# Interfaces.net
KiCad netlist of a schematic drawn in Altium Designer
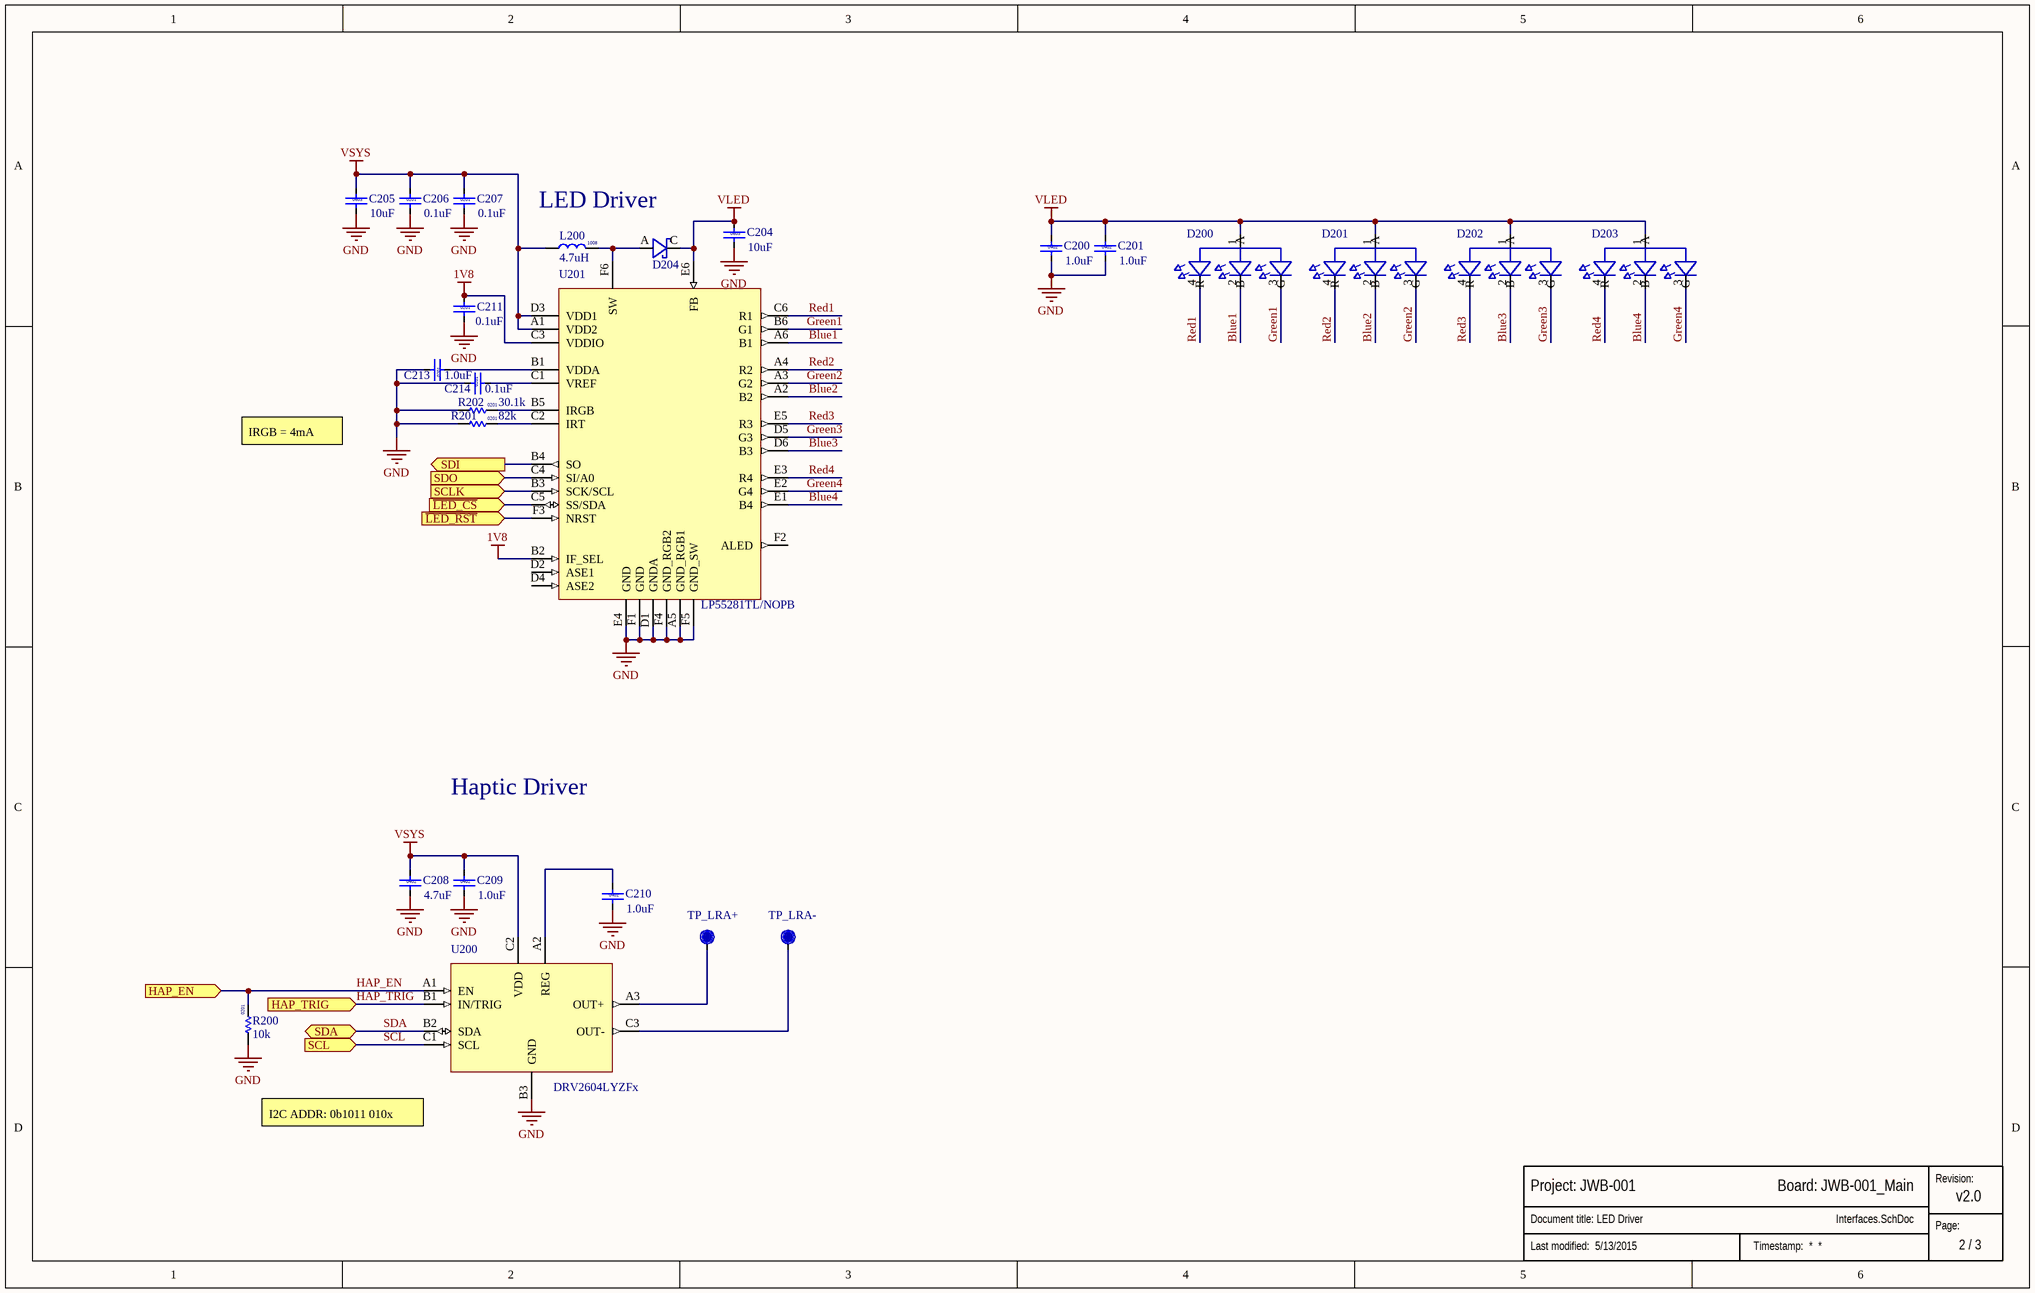
[diagram p0: Interfaces.SchDoc]

(export (version "E")
  (design (tool "Eeschema 10.0.6"))
  (components
    (comp (ref "C200")
      (value "1.0uF")
      (footprint "Cap 0402 HD")
      (description "Cap, Ceramic 1.0uF 10V 10% X5R 0402")
      (fields
        (field (name "SIZE") "0402")
        (field (name "PART NUMBER") "Cap 0402 1.0uF 10V")
        (field (name "TOLERANCE") "10%")
        (field (name "ADDED BY") "Jeremy D")
        (field (name "CHECKED BY") "Paul B")
      )
      (libsource (lib "Rigado_AltiumLib") (part "Cap Chip"))
    )
    (comp (ref "C201")
      (value "1.0uF")
      (footprint "Cap 0402 HD")
      (description "Cap, Ceramic 1.0uF 10V 10% X5R 0402")
      (fields
        (field (name "SIZE") "0402")
        (field (name "PART NUMBER") "Cap 0402 1.0uF 10V")
        (field (name "TOLERANCE") "10%")
        (field (name "ADDED BY") "Jeremy D")
        (field (name "CHECKED BY") "Paul B")
      )
      (libsource (lib "Rigado_AltiumLib") (part "Cap Chip"))
    )
    (comp (ref "C204")
      (value "10uF")
      (footprint "Cap 0603")
      (description "Cap, Ceramimic 10uF 10V 20% X5R 0603")
      (fields
        (field (name "SIZE") "0603")
        (field (name "PART NUMBER") "Cap 0603 10uF 10V")
        (field (name "TOLERANCE") "20%")
        (field (name "ADDED BY") "Jeremy D")
        (field (name "CHECKED BY") "Cam N")
      )
      (libsource (lib "Rigado_AltiumLib") (part "Cap Chip"))
    )
    (comp (ref "C205")
      (value "10uF")
      (footprint "Cap 0603")
      (description "Cap, Ceramimic 10uF 10V 20% X5R 0603")
      (fields
        (field (name "SIZE") "0603")
        (field (name "PART NUMBER") "Cap 0603 10uF 10V")
        (field (name "TOLERANCE") "20%")
        (field (name "ADDED BY") "Jeremy D")
        (field (name "CHECKED BY") "Cam N")
      )
      (libsource (lib "Rigado_AltiumLib") (part "Cap Chip"))
    )
    (comp (ref "C206")
      (value "0.1uF")
      (footprint "Cap 0201 HD")
      (description "Cap, Ceramic 0.1uF 6.3V 10% X5R  0201")
      (fields
        (field (name "SIZE") "0201")
        (field (name "PART NUMBER") "Cap 0201 0.1uF 6.3V")
        (field (name "TOLERANCE") "10%")
        (field (name "ADDED BY") "Jeremy D")
        (field (name "CHECKED BY") "Cam N")
      )
      (libsource (lib "Rigado_AltiumLib") (part "Cap Chip"))
    )
    (comp (ref "C207")
      (value "0.1uF")
      (footprint "Cap 0201 HD")
      (description "Cap, Ceramic 0.1uF 6.3V 10% X5R  0201")
      (fields
        (field (name "SIZE") "0201")
        (field (name "PART NUMBER") "Cap 0201 0.1uF 6.3V")
        (field (name "TOLERANCE") "10%")
        (field (name "ADDED BY") "Jeremy D")
        (field (name "CHECKED BY") "Cam N")
      )
      (libsource (lib "Rigado_AltiumLib") (part "Cap Chip"))
    )
    (comp (ref "C208")
      (value "4.7uF")
      (footprint "Cap 0402 HD")
      (description "Cap, Ceramic 4.7uF 10V 20% X5R 0402")
      (fields
        (field (name "SIZE") "0402")
        (field (name "PART NUMBER") "Cap 0402 4.7uF 10V")
        (field (name "TOLERANCE") "20%")
        (field (name "ADDED BY") "Jeremy D")
        (field (name "CHECKED BY") "Paul B")
      )
      (libsource (lib "Rigado_AltiumLib") (part "Cap Chip"))
    )
    (comp (ref "C209")
      (value "1.0uF")
      (footprint "Cap 0402 HD")
      (description "Cap, Ceramic 1.0uF 10V 10% X5R 0402")
      (fields
        (field (name "SIZE") "0402")
        (field (name "PART NUMBER") "Cap 0402 1.0uF 10V")
        (field (name "TOLERANCE") "10%")
        (field (name "ADDED BY") "Jeremy D")
        (field (name "CHECKED BY") "Paul B")
      )
      (libsource (lib "Rigado_AltiumLib") (part "Cap Chip"))
    )
    (comp (ref "C210")
      (value "1.0uF")
      (footprint "Cap 0402 HD")
      (description "Cap, Ceramic 1.0uF 10V 10% X5R 0402")
      (fields
        (field (name "SIZE") "0402")
        (field (name "PART NUMBER") "Cap 0402 1.0uF 10V")
        (field (name "TOLERANCE") "10%")
        (field (name "ADDED BY") "Jeremy D")
        (field (name "CHECKED BY") "Paul B")
      )
      (libsource (lib "Rigado_AltiumLib") (part "Cap Chip"))
    )
    (comp (ref "C211")
      (value "0.1uF")
      (footprint "Cap 0201 HD")
      (description "Cap, Ceramic 0.1uF 6.3V 10% X5R  0201")
      (fields
        (field (name "SIZE") "0201")
        (field (name "PART NUMBER") "Cap 0201 0.1uF 6.3V")
        (field (name "TOLERANCE") "10%")
        (field (name "ADDED BY") "Jeremy D")
        (field (name "CHECKED BY") "Cam N")
      )
      (libsource (lib "Rigado_AltiumLib") (part "Cap Chip"))
    )
    (comp (ref "C213")
      (value "1.0uF")
      (footprint "Cap 0201 HD")
      (description "Cap, Ceramic 1.0uF 6.3V 20% X5R  0201")
      (fields
        (field (name "SIZE") "0201")
        (field (name "PART NUMBER") "Cap 0201 1.0uF 6.3V")
        (field (name "TOLERANCE") "20%")
        (field (name "ADDED BY") "Jeremy D")
        (field (name "CHECKED BY") "Cam N")
      )
      (libsource (lib "Rigado_AltiumLib") (part "Cap Chip"))
    )
    (comp (ref "C214")
      (value "0.1uF")
      (footprint "Cap 0201 HD")
      (description "Cap, Ceramic 0.1uF 6.3V 10% X5R  0201")
      (fields
        (field (name "SIZE") "0201")
        (field (name "PART NUMBER") "Cap 0201 0.1uF 6.3V")
        (field (name "TOLERANCE") "10%")
        (field (name "ADDED BY") "Jeremy D")
        (field (name "CHECKED BY") "Cam N")
      )
      (libsource (lib "Rigado_AltiumLib") (part "Cap Chip"))
    )
    (comp (ref "D200")
      (value "CLMVB-FKA-CFHEHLCBB7A363")
      (footprint "4-PLCC")
      (description "RGB LED SMD, Diffused")
      (fields
        (field (name "MANUFACTURER") "Cree")
        (field (name "ADDED BY") "Jeremy D")
        (field (name "CHECKED BY") "Cam N")
      )
      (libsource (lib "Rigado_AltiumLib") (part "LED_RGB_CA_2"))
    )
    (comp (ref "D201")
      (value "CLMVB-FKA-CFHEHLCBB7A363")
      (footprint "4-PLCC")
      (description "RGB LED SMD, Diffused")
      (fields
        (field (name "MANUFACTURER") "Cree")
        (field (name "ADDED BY") "Jeremy D")
        (field (name "CHECKED BY") "Cam N")
      )
      (libsource (lib "Rigado_AltiumLib") (part "LED_RGB_CA_2"))
    )
    (comp (ref "D202")
      (value "CLMVB-FKA-CFHEHLCBB7A363")
      (footprint "4-PLCC")
      (description "RGB LED SMD, Diffused")
      (fields
        (field (name "MANUFACTURER") "Cree")
        (field (name "ADDED BY") "Jeremy D")
        (field (name "CHECKED BY") "Cam N")
      )
      (libsource (lib "Rigado_AltiumLib") (part "LED_RGB_CA_2"))
    )
    (comp (ref "D203")
      (value "CLMVB-FKA-CFHEHLCBB7A363")
      (footprint "4-PLCC")
      (description "RGB LED SMD, Diffused")
      (fields
        (field (name "MANUFACTURER") "Cree")
        (field (name "ADDED BY") "Jeremy D")
        (field (name "CHECKED BY") "Cam N")
      )
      (libsource (lib "Rigado_AltiumLib") (part "LED_RGB_CA_2"))
    )
    (comp (ref "D204")
      (value "MBR120VLSFT3G20V")
      (footprint "SOD-123F_U")
      (description "Diode, Schottky, 20V 1A SOD-123F, 340mV Vf @ 1A")
      (fields
        (field (name "PART NUMBER") "MBR120VLSFT3G")
        (field (name "MANUFACTURER") "ON Semi")
        (field (name "ADDED BY") "Jeremy D")
      )
      (libsource (lib "LOCAL_Rigado_AltiumLib") (part "Diode_Schottky"))
    )
    (comp (ref "L200")
      (value "4.7uH")
      (footprint "IND 1008")
      (description "Inductor, 4.7uH, 1008")
      (fields
        (field (name "SIZE") "1008")
        (field (name "PART NUMBER") "Ind 1008 4.7uH 650mA")
        (field (name "MANUFACTURER") "Samsung")
        (field (name "ADDED BY") "Jeremy D")
        (field (name "CHECKED BY") "Cam N")
      )
      (libsource (lib "Rigado_AltiumLib") (part "Ind sm"))
    )
    (comp (ref "R200")
      (value "10k")
      (footprint "RES 0201 HD")
      (description "Resistor 10k ohm 5% 1/20W 0201")
      (fields
        (field (name "SIZE") "0201")
        (field (name "PART NUMBER") "Res 0201 10k 5%")
        (field (name "MANUFACTURER") "Rohm")
        (field (name "ADDED BY") "Jeremy D")
        (field (name "CHECKED BY") "Paul B")
      )
      (libsource (lib "Rigado_AltiumLib") (part "Res sm"))
    )
    (comp (ref "R201")
      (value "82k")
      (footprint "RES 0201 HD")
      (description "Resistor, 0201")
      (fields
        (field (name "SIZE") "0201")
        (field (name "PART NUMBER") "Res 0201 Generic")
        (field (name "Comment") "Res 0201 Generic82k")
        (field (name "ADDED BY") "Jeremy D")
        (field (name "CHECKED BY") "Paul B")
      )
      (libsource (lib "Rigado_AltiumLib") (part "Res sm"))
    )
    (comp (ref "R202")
      (value "30.1k")
      (footprint "RES 0201 HD")
      (description "Resistor, 0201")
      (fields
        (field (name "SIZE") "0201")
        (field (name "PART NUMBER") "Res 0201 Generic")
        (field (name "Comment") "Res 0201 Generic30.1k")
        (field (name "ADDED BY") "Jeremy D")
        (field (name "CHECKED BY") "Paul B")
      )
      (libsource (lib "Rigado_AltiumLib") (part "Res sm"))
    )
    (comp (ref "TP_LRA+")
      (value "TP")
      (footprint "TP17R")
      (description "Testpoint, Round 1.7mm Dia")
      (fields
        (field (name "PART NUMBER") "TP17R")
        (field (name "ADDED BY") "Jeremy D")
        (field (name "CHECKED BY") "Paul B")
      )
      (libsource (lib "LOCAL_Rigado_AltiumLib") (part "TP_R"))
    )
    (comp (ref "TP_LRA-")
      (value "TP")
      (footprint "TP17R")
      (description "Testpoint, Round 1.7mm Dia")
      (fields
        (field (name "PART NUMBER") "TP17R")
        (field (name "ADDED BY") "Jeremy D")
        (field (name "CHECKED BY") "Paul B")
      )
      (libsource (lib "LOCAL_Rigado_AltiumLib") (part "TP_R"))
    )
    (comp (ref "U200")
      (value "DRV2604L")
      (footprint "BGA0.5P3x3-9Pin")
      (description "Haptic Driver w/Internal Memory, I2C, DSBGA 9")
      (fields
        (field (name "MANUFACTURER P/N") "DRV2604LYZFx")
        (field (name "MANUFACTURER") "Texas Instruments")
        (field (name "ADDED BY") "Jeremy D")
        (field (name "CHECKED BY") "Paul B")
      )
      (libsource (lib "Rigado_AltiumLib") (part "DRV2604L"))
    )
    (comp (ref "U201")
      (value "LP55281TL")
      (footprint "BGA0.5P6x6-36Pin")
      (description "Quad RGB LED driver w/integrated boost supply and audio sync")
      (fields
        (field (name "MANUFACTURER P/N") "LP55281TL/NOPB")
        (field (name "MANUFACTURER") "Texas Instruments")
        (field (name "ADDED BY") "Jeremy D")
        (field (name "CHECKED BY") "Paul B")
      )
      (libsource (lib "Rigado_AltiumLib") (part "LP55281"))
    )
  )
  (nets
    (net (code "1") (name "/Blue1") (class "Default")
      (node (ref "D200") (pin "2") (pinfunction "B_2") (pintype "passive"))
      (node (ref "U201") (pin "A6") (pinfunction "B1_A6") (pintype "output"))
    )
    (net (code "2") (name "/Blue2") (class "Default")
      (node (ref "D201") (pin "2") (pinfunction "B_2") (pintype "passive"))
      (node (ref "U201") (pin "A2") (pinfunction "B2_A2") (pintype "output"))
    )
    (net (code "3") (name "/Blue3") (class "Default")
      (node (ref "D202") (pin "2") (pinfunction "B_2") (pintype "passive"))
      (node (ref "U201") (pin "D6") (pinfunction "B3_D6") (pintype "output"))
    )
    (net (code "4") (name "/Blue4") (class "Default")
      (node (ref "D203") (pin "2") (pinfunction "B_2") (pintype "passive"))
      (node (ref "U201") (pin "E1") (pinfunction "B4_E1") (pintype "output"))
    )
    (net (code "5") (name "/Green1") (class "Default")
      (node (ref "D200") (pin "3") (pinfunction "G_3") (pintype "passive"))
      (node (ref "U201") (pin "B6") (pinfunction "G1_B6") (pintype "output"))
    )
    (net (code "6") (name "/Green2") (class "Default")
      (node (ref "D201") (pin "3") (pinfunction "G_3") (pintype "passive"))
      (node (ref "U201") (pin "A3") (pinfunction "G2_A3") (pintype "output"))
    )
    (net (code "7") (name "/Green3") (class "Default")
      (node (ref "D202") (pin "3") (pinfunction "G_3") (pintype "passive"))
      (node (ref "U201") (pin "D5") (pinfunction "G3_D5") (pintype "output"))
    )
    (net (code "8") (name "/Green4") (class "Default")
      (node (ref "D203") (pin "3") (pinfunction "G_3") (pintype "passive"))
      (node (ref "U201") (pin "E2") (pinfunction "G4_E2") (pintype "output"))
    )
    (net (code "9") (name "/HAP_EN") (class "Default")
      (node (ref "R200") (pin "2") (pinfunction "2_2") (pintype "passive"))
      (node (ref "U200") (pin "A1") (pinfunction "EN_A1") (pintype "input"))
    )
    (net (code "10") (name "/HAP_TRIG") (class "Default")
      (node (ref "U200") (pin "B1") (pinfunction "IN/TRIG_B1") (pintype "input"))
    )
    (net (code "11") (name "/LED_CS") (class "Default")
      (node (ref "U201") (pin "C5") (pinfunction "SS/SDA_C5") (pintype "bidirectional"))
    )
    (net (code "12") (name "/LED_RST") (class "Default")
      (node (ref "U201") (pin "F3") (pinfunction "NRST_F3") (pintype "input"))
    )
    (net (code "13") (name "/Red1") (class "Default")
      (node (ref "D200") (pin "4") (pinfunction "R_4") (pintype "passive"))
      (node (ref "U201") (pin "C6") (pinfunction "R1_C6") (pintype "output"))
    )
    (net (code "14") (name "/Red2") (class "Default")
      (node (ref "D201") (pin "4") (pinfunction "R_4") (pintype "passive"))
      (node (ref "U201") (pin "A4") (pinfunction "R2_A4") (pintype "output"))
    )
    (net (code "15") (name "/Red3") (class "Default")
      (node (ref "D202") (pin "4") (pinfunction "R_4") (pintype "passive"))
      (node (ref "U201") (pin "E5") (pinfunction "R3_E5") (pintype "output"))
    )
    (net (code "16") (name "/Red4") (class "Default")
      (node (ref "D203") (pin "4") (pinfunction "R_4") (pintype "passive"))
      (node (ref "U201") (pin "E3") (pinfunction "R4_E3") (pintype "output"))
    )
    (net (code "17") (name "/SCL") (class "Default")
      (node (ref "U200") (pin "C1") (pinfunction "SCL_C1") (pintype "input"))
    )
    (net (code "18") (name "/SCLK") (class "Default")
      (node (ref "U201") (pin "B3") (pinfunction "SCK/SCL_B3") (pintype "input"))
    )
    (net (code "19") (name "/SDA") (class "Default")
      (node (ref "U200") (pin "B2") (pinfunction "SDA_B2") (pintype "bidirectional"))
    )
    (net (code "20") (name "/SDI") (class "Default")
      (node (ref "U201") (pin "B4") (pinfunction "SO_B4") (pintype "output"))
    )
    (net (code "21") (name "/SDO") (class "Default")
      (node (ref "U201") (pin "C4") (pinfunction "SI/A0_C4") (pintype "input"))
    )
    (net (code "22") (name "1V8") (class "Default")
      (node (ref "C211") (pin "1") (pinfunction "1_1") (pintype "passive"))
      (node (ref "U201") (pin "B2") (pinfunction "IF_SEL_B2") (pintype "input"))
      (node (ref "U201") (pin "C3") (pinfunction "VDDIO_C3") (pintype "power_in"))
    )
    (net (code "23") (name "GND") (class "Default")
      (node (ref "C200") (pin "2") (pinfunction "2_2") (pintype "passive"))
      (node (ref "C201") (pin "2") (pinfunction "2_2") (pintype "passive"))
      (node (ref "C204") (pin "2") (pinfunction "2_2") (pintype "passive"))
      (node (ref "C205") (pin "2") (pinfunction "2_2") (pintype "passive"))
      (node (ref "C206") (pin "2") (pinfunction "2_2") (pintype "passive"))
      (node (ref "C207") (pin "2") (pinfunction "2_2") (pintype "passive"))
      (node (ref "C208") (pin "2") (pinfunction "2_2") (pintype "passive"))
      (node (ref "C209") (pin "2") (pinfunction "2_2") (pintype "passive"))
      (node (ref "C210") (pin "2") (pinfunction "2_2") (pintype "passive"))
      (node (ref "C211") (pin "2") (pinfunction "2_2") (pintype "passive"))
      (node (ref "C213") (pin "2") (pinfunction "2_2") (pintype "passive"))
      (node (ref "C214") (pin "1") (pinfunction "1_1") (pintype "passive"))
      (node (ref "R200") (pin "1") (pinfunction "1_1") (pintype "passive"))
      (node (ref "R201") (pin "1") (pinfunction "1_1") (pintype "passive"))
      (node (ref "R202") (pin "1") (pinfunction "1_1") (pintype "passive"))
      (node (ref "U200") (pin "B3") (pinfunction "GND_B3") (pintype "power_in"))
      (node (ref "U201") (pin "A5") (pinfunction "GND_RGB1_A5") (pintype "power_in"))
      (node (ref "U201") (pin "D1") (pinfunction "GNDA_D1") (pintype "power_in"))
      (node (ref "U201") (pin "E4") (pinfunction "GND_E4") (pintype "power_in"))
      (node (ref "U201") (pin "F1") (pinfunction "GND_F1") (pintype "power_in"))
      (node (ref "U201") (pin "F4") (pinfunction "GND_RGB2_F4") (pintype "power_in"))
      (node (ref "U201") (pin "F5") (pinfunction "GND_SW_F5") (pintype "power_in"))
    )
    (net (code "24") (name "Net-(U200-OUT+)") (class "Default")
      (node (ref "TP_LRA+") (pin "1") (pintype "passive"))
      (node (ref "U200") (pin "A3") (pinfunction "OUT+_A3") (pintype "output"))
    )
    (net (code "25") (name "Net-(U200-OUT-)") (class "Default")
      (node (ref "TP_LRA-") (pin "1") (pintype "passive"))
      (node (ref "U200") (pin "C3") (pinfunction "OUT-_C3") (pintype "output"))
    )
    (net (code "26") (name "Net-(U200-REG)") (class "Default")
      (node (ref "C210") (pin "1") (pinfunction "1_1") (pintype "passive"))
      (node (ref "U200") (pin "A2") (pinfunction "REG_A2") (pintype "power_in"))
    )
    (net (code "27") (name "Net-(U201-IRGB)") (class "Default")
      (node (ref "R202") (pin "2") (pinfunction "2_2") (pintype "passive"))
      (node (ref "U201") (pin "B5") (pinfunction "IRGB_B5") (pintype "passive"))
    )
    (net (code "28") (name "Net-(U201-IRT)") (class "Default")
      (node (ref "R201") (pin "2") (pinfunction "2_2") (pintype "passive"))
      (node (ref "U201") (pin "C2") (pinfunction "IRT_C2") (pintype "passive"))
    )
    (net (code "29") (name "Net-(U201-SW)") (class "Default")
      (node (ref "D204") (pin "A") (pintype "passive"))
      (node (ref "L200") (pin "2") (pinfunction "2_2") (pintype "passive"))
      (node (ref "U201") (pin "F6") (pinfunction "SW_F6") (pintype "power_in"))
    )
    (net (code "30") (name "Net-(U201-VDDA)") (class "Default")
      (node (ref "C213") (pin "1") (pinfunction "1_1") (pintype "passive"))
      (node (ref "U201") (pin "B1") (pinfunction "VDDA_B1") (pintype "power_in"))
    )
    (net (code "31") (name "Net-(U201-VREF)") (class "Default")
      (node (ref "C214") (pin "2") (pinfunction "2_2") (pintype "passive"))
      (node (ref "U201") (pin "C1") (pinfunction "VREF_C1") (pintype "passive"))
    )
    (net (code "32") (name "VLED") (class "Default")
      (node (ref "C200") (pin "1") (pinfunction "1_1") (pintype "passive"))
      (node (ref "C201") (pin "1") (pinfunction "1_1") (pintype "passive"))
      (node (ref "C204") (pin "1") (pinfunction "1_1") (pintype "passive"))
      (node (ref "D200") (pin "1") (pinfunction "A_1") (pintype "passive"))
      (node (ref "D201") (pin "1") (pinfunction "A_1") (pintype "passive"))
      (node (ref "D202") (pin "1") (pinfunction "A_1") (pintype "passive"))
      (node (ref "D203") (pin "1") (pinfunction "A_1") (pintype "passive"))
      (node (ref "D204") (pin "C") (pintype "passive"))
      (node (ref "U201") (pin "E6") (pinfunction "FB_E6") (pintype "input"))
    )
    (net (code "33") (name "VSYS") (class "Default")
      (node (ref "C205") (pin "1") (pinfunction "1_1") (pintype "passive"))
      (node (ref "C206") (pin "1") (pinfunction "1_1") (pintype "passive"))
      (node (ref "C207") (pin "1") (pinfunction "1_1") (pintype "passive"))
      (node (ref "C208") (pin "1") (pinfunction "1_1") (pintype "passive"))
      (node (ref "C209") (pin "1") (pinfunction "1_1") (pintype "passive"))
      (node (ref "L200") (pin "1") (pinfunction "1_1") (pintype "passive"))
      (node (ref "U200") (pin "C2") (pinfunction "VDD_C2") (pintype "power_in"))
      (node (ref "U201") (pin "A1") (pinfunction "VDD2_A1") (pintype "power_in"))
      (node (ref "U201") (pin "D3") (pinfunction "VDD1_D3") (pintype "power_in"))
    )
    (net (code "34") (name "unconnected-(U201-ALED-PadF2)") (class "Default")
      (node (ref "U201") (pin "F2") (pinfunction "ALED_F2") (pintype "output"))
    )
    (net (code "35") (name "unconnected-(U201-ASE1-PadD2)") (class "Default")
      (node (ref "U201") (pin "D2") (pinfunction "ASE1_D2") (pintype "input"))
    )
    (net (code "36") (name "unconnected-(U201-ASE2-PadD4)") (class "Default")
      (node (ref "U201") (pin "D4") (pinfunction "ASE2_D4") (pintype "input"))
    )
  )
)
